# CONNECTORS.net
KiCad netlist of a schematic drawn in Altium Designer
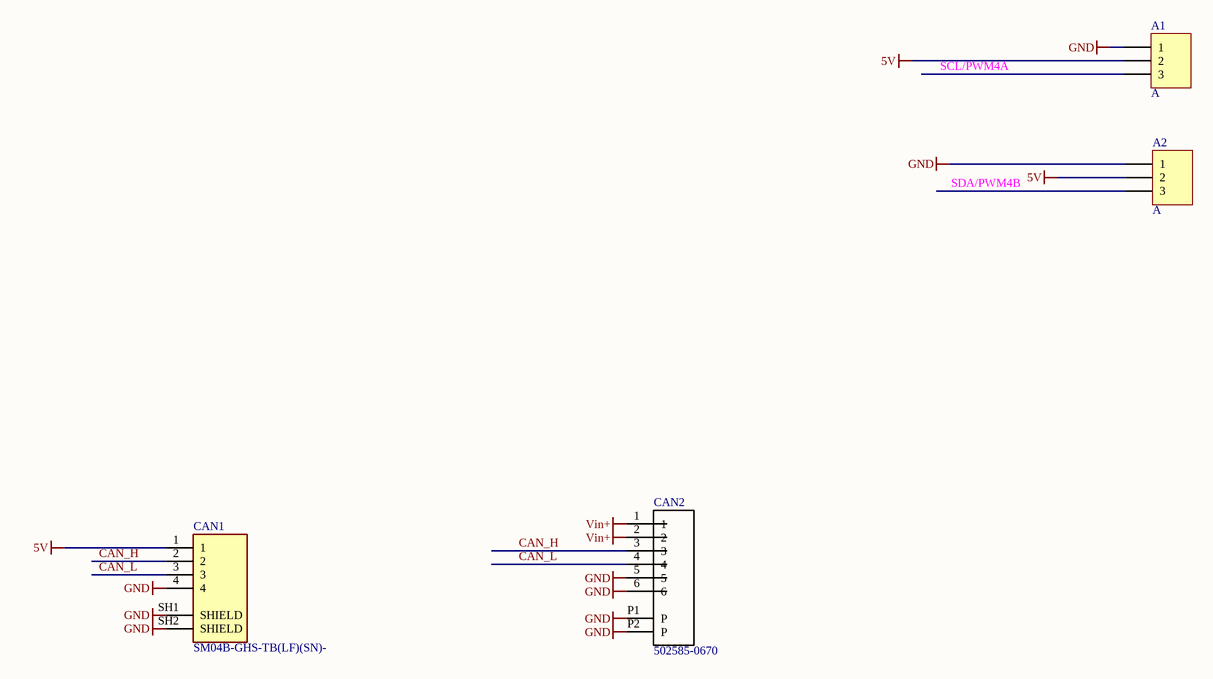
[diagram p0: CONNECTORS.SchDoc]

(export (version "E")
  (design (tool "Eeschema 10.0.6"))
  (components
    (comp (ref "A1")
      (value "A")
      (footprint "HDR Side 3 pin")
      (description "Header, 4-Pin")
      (fields (field (name "MF") "Connfly electronic (Zhenqin)") (field (name "MP") "PLS-3 (DS1021-1x3)"))
      (libsource (lib "DC_DC") (part "Header 3"))
    )
    (comp (ref "A2")
      (value "A")
      (footprint "HDR Side 3 pin")
      (description "Header, 4-Pin")
      (fields (field (name "MF") "Connfly electronic (Zhenqin)") (field (name "MP") "PLS-3 (DS1021-1x3)"))
      (libsource (lib "DC_DC") (part "Header 3"))
    )
    (comp (ref "CAN1")
      (value "SM04B-GHS-TB(LF)(SN)-")
      (footprint "JST_SM04B-GHS-TB(LF)(SN)-")
      (description "Connector Header Surface Mount, Right Angle 4 position 0.049 _1.25mm_")
      (fields (field (name "MP") "SM04B-GHS-TB_LF__SN_-") (field (name "MF") "JST Sales"))
      (libsource (lib "lib") (part "SM04B-GHS-TB(LF)(SN)-"))
    )
    (comp (ref "CAN2")
      (value "502585-0670")
      (footprint "MOLEX_502585-0670")
      (fields (field (name "MP") "502494-0670") (field (name "MF") "Molex"))
      (libsource (lib "lib") (part "502585-0670"))
    )
  )
  (nets
    (net (code "1") (name "/CAN_H") (class "Default")
      (node (ref "CAN1") (pin "2") (pinfunction "2_2") (pintype "passive"))
      (node (ref "CAN2") (pin "3") (pinfunction "3_3") (pintype "passive"))
    )
    (net (code "2") (name "/CAN_L") (class "Default")
      (node (ref "CAN1") (pin "3") (pinfunction "3_3") (pintype "passive"))
      (node (ref "CAN2") (pin "4") (pinfunction "4_4") (pintype "passive"))
    )
    (net (code "3") (name "/SCL{slash}PWM4A") (class "Default")
      (node (ref "A1") (pin "3") (pinfunction "3_3") (pintype "passive"))
    )
    (net (code "4") (name "/SDA{slash}PWM4B") (class "Default")
      (node (ref "A2") (pin "3") (pinfunction "3_3") (pintype "passive"))
    )
    (net (code "5") (name "5V") (class "Default")
      (node (ref "A1") (pin "2") (pinfunction "2_2") (pintype "passive"))
      (node (ref "A2") (pin "2") (pinfunction "2_2") (pintype "passive"))
      (node (ref "CAN1") (pin "1") (pinfunction "1_1") (pintype "passive"))
    )
    (net (code "6") (name "GND") (class "Default")
      (node (ref "A1") (pin "1") (pinfunction "1_1") (pintype "passive"))
      (node (ref "A2") (pin "1") (pinfunction "1_1") (pintype "passive"))
      (node (ref "CAN1") (pin "4") (pinfunction "4_4") (pintype "passive"))
      (node (ref "CAN1") (pin "SH1") (pinfunction "SHIELD_SH1") (pintype "power_in"))
      (node (ref "CAN1") (pin "SH2") (pinfunction "SHIELD_SH2") (pintype "power_in"))
      (node (ref "CAN2") (pin "5") (pinfunction "5_5") (pintype "passive"))
      (node (ref "CAN2") (pin "6") (pinfunction "6_6") (pintype "passive"))
      (node (ref "CAN2") (pin "P1") (pinfunction "P_P1") (pintype "passive"))
      (node (ref "CAN2") (pin "P2") (pinfunction "P_P2") (pintype "passive"))
    )
    (net (code "7") (name "Vin+") (class "Default")
      (node (ref "CAN2") (pin "1") (pinfunction "1_1") (pintype "passive"))
      (node (ref "CAN2") (pin "2") (pinfunction "2_2") (pintype "passive"))
    )
  )
)
